# wheatstone_bridge_board.net
KiCad netlist of a schematic drawn in EAGLE
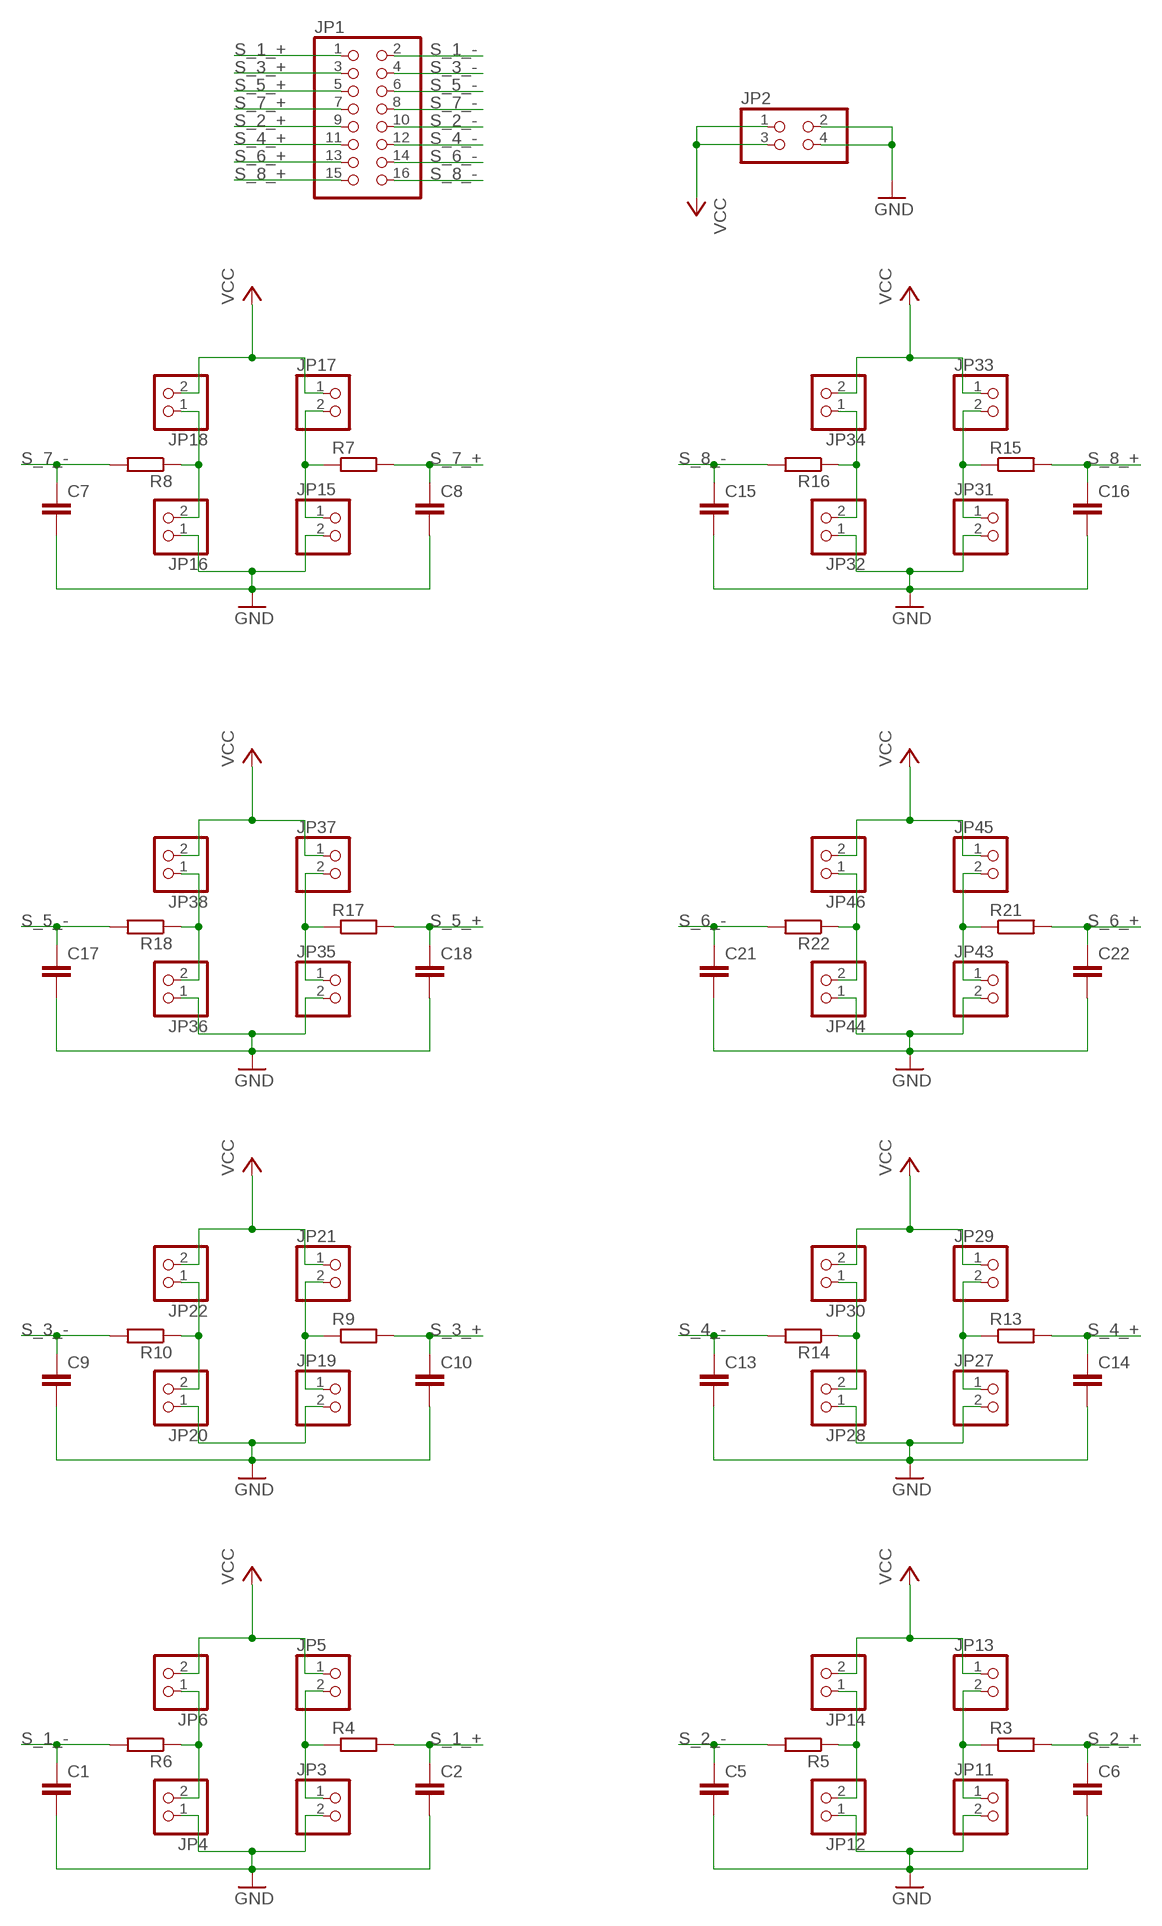
[diagram p0: schematic, sheet 1]

(export (version "E")
  (design (tool "Eeschema 10.0.6"))
  (components
    (comp (ref "C1")
      (value "C-EU025-050X050")
      (footprint "eagle-import:C025-050X050")
      (libsource (lib "eagle-import") (part "C-EU025-050X050"))
    )
    (comp (ref "C2")
      (value "C-EU025-050X050")
      (footprint "eagle-import:C025-050X050")
      (libsource (lib "eagle-import") (part "C-EU025-050X050"))
    )
    (comp (ref "C5")
      (value "C-EU025-050X050")
      (footprint "eagle-import:C025-050X050")
      (libsource (lib "eagle-import") (part "C-EU025-050X050"))
    )
    (comp (ref "C6")
      (value "C-EU025-050X050")
      (footprint "eagle-import:C025-050X050")
      (libsource (lib "eagle-import") (part "C-EU025-050X050"))
    )
    (comp (ref "C7")
      (value "C-EU025-050X050")
      (footprint "eagle-import:C025-050X050")
      (libsource (lib "eagle-import") (part "C-EU025-050X050"))
    )
    (comp (ref "C8")
      (value "C-EU025-050X050")
      (footprint "eagle-import:C025-050X050")
      (libsource (lib "eagle-import") (part "C-EU025-050X050"))
    )
    (comp (ref "C9")
      (value "C-EU025-050X050")
      (footprint "eagle-import:C025-050X050")
      (libsource (lib "eagle-import") (part "C-EU025-050X050"))
    )
    (comp (ref "C10")
      (value "C-EU025-050X050")
      (footprint "eagle-import:C025-050X050")
      (libsource (lib "eagle-import") (part "C-EU025-050X050"))
    )
    (comp (ref "C13")
      (value "C-EU025-050X050")
      (footprint "eagle-import:C025-050X050")
      (libsource (lib "eagle-import") (part "C-EU025-050X050"))
    )
    (comp (ref "C14")
      (value "C-EU025-050X050")
      (footprint "eagle-import:C025-050X050")
      (libsource (lib "eagle-import") (part "C-EU025-050X050"))
    )
    (comp (ref "C15")
      (value "C-EU025-050X050")
      (footprint "eagle-import:C025-050X050")
      (libsource (lib "eagle-import") (part "C-EU025-050X050"))
    )
    (comp (ref "C16")
      (value "C-EU025-050X050")
      (footprint "eagle-import:C025-050X050")
      (libsource (lib "eagle-import") (part "C-EU025-050X050"))
    )
    (comp (ref "C17")
      (value "C-EU025-050X050")
      (footprint "eagle-import:C025-050X050")
      (libsource (lib "eagle-import") (part "C-EU025-050X050"))
    )
    (comp (ref "C18")
      (value "C-EU025-050X050")
      (footprint "eagle-import:C025-050X050")
      (libsource (lib "eagle-import") (part "C-EU025-050X050"))
    )
    (comp (ref "C21")
      (value "C-EU025-050X050")
      (footprint "eagle-import:C025-050X050")
      (libsource (lib "eagle-import") (part "C-EU025-050X050"))
    )
    (comp (ref "C22")
      (value "C-EU025-050X050")
      (footprint "eagle-import:C025-050X050")
      (libsource (lib "eagle-import") (part "C-EU025-050X050"))
    )
    (comp (ref "JP1")
      (value "PINHD-2X8/90")
      (footprint "eagle-import:2X08_90")
      (libsource (lib "eagle-import") (part "PINHD-2X8/90"))
    )
    (comp (ref "JP2")
      (value "PINHD-2X2/90")
      (footprint "eagle-import:2X02_90")
      (libsource (lib "eagle-import") (part "PINHD-2X2/90"))
    )
    (comp (ref "JP3")
      (value "PINHD-1X2")
      (footprint "eagle-import:1X02")
      (libsource (lib "eagle-import") (part "PINHD-1X2"))
    )
    (comp (ref "JP4")
      (value "PINHD-1X2")
      (footprint "eagle-import:1X02")
      (libsource (lib "eagle-import") (part "PINHD-1X2"))
    )
    (comp (ref "JP5")
      (value "PINHD-1X2")
      (footprint "eagle-import:1X02")
      (libsource (lib "eagle-import") (part "PINHD-1X2"))
    )
    (comp (ref "JP6")
      (value "PINHD-1X2")
      (footprint "eagle-import:1X02")
      (libsource (lib "eagle-import") (part "PINHD-1X2"))
    )
    (comp (ref "JP11")
      (value "PINHD-1X2")
      (footprint "eagle-import:1X02")
      (libsource (lib "eagle-import") (part "PINHD-1X2"))
    )
    (comp (ref "JP12")
      (value "PINHD-1X2")
      (footprint "eagle-import:1X02")
      (libsource (lib "eagle-import") (part "PINHD-1X2"))
    )
    (comp (ref "JP13")
      (value "PINHD-1X2")
      (footprint "eagle-import:1X02")
      (libsource (lib "eagle-import") (part "PINHD-1X2"))
    )
    (comp (ref "JP14")
      (value "PINHD-1X2")
      (footprint "eagle-import:1X02")
      (libsource (lib "eagle-import") (part "PINHD-1X2"))
    )
    (comp (ref "JP15")
      (value "PINHD-1X2")
      (footprint "eagle-import:1X02")
      (libsource (lib "eagle-import") (part "PINHD-1X2"))
    )
    (comp (ref "JP16")
      (value "PINHD-1X2")
      (footprint "eagle-import:1X02")
      (libsource (lib "eagle-import") (part "PINHD-1X2"))
    )
    (comp (ref "JP17")
      (value "PINHD-1X2")
      (footprint "eagle-import:1X02")
      (libsource (lib "eagle-import") (part "PINHD-1X2"))
    )
    (comp (ref "JP18")
      (value "PINHD-1X2")
      (footprint "eagle-import:1X02")
      (libsource (lib "eagle-import") (part "PINHD-1X2"))
    )
    (comp (ref "JP19")
      (value "PINHD-1X2")
      (footprint "eagle-import:1X02")
      (libsource (lib "eagle-import") (part "PINHD-1X2"))
    )
    (comp (ref "JP20")
      (value "PINHD-1X2")
      (footprint "eagle-import:1X02")
      (libsource (lib "eagle-import") (part "PINHD-1X2"))
    )
    (comp (ref "JP21")
      (value "PINHD-1X2")
      (footprint "eagle-import:1X02")
      (libsource (lib "eagle-import") (part "PINHD-1X2"))
    )
    (comp (ref "JP22")
      (value "PINHD-1X2")
      (footprint "eagle-import:1X02")
      (libsource (lib "eagle-import") (part "PINHD-1X2"))
    )
    (comp (ref "JP27")
      (value "PINHD-1X2")
      (footprint "eagle-import:1X02")
      (libsource (lib "eagle-import") (part "PINHD-1X2"))
    )
    (comp (ref "JP28")
      (value "PINHD-1X2")
      (footprint "eagle-import:1X02")
      (libsource (lib "eagle-import") (part "PINHD-1X2"))
    )
    (comp (ref "JP29")
      (value "PINHD-1X2")
      (footprint "eagle-import:1X02")
      (libsource (lib "eagle-import") (part "PINHD-1X2"))
    )
    (comp (ref "JP30")
      (value "PINHD-1X2")
      (footprint "eagle-import:1X02")
      (libsource (lib "eagle-import") (part "PINHD-1X2"))
    )
    (comp (ref "JP31")
      (value "PINHD-1X2")
      (footprint "eagle-import:1X02")
      (libsource (lib "eagle-import") (part "PINHD-1X2"))
    )
    (comp (ref "JP32")
      (value "PINHD-1X2")
      (footprint "eagle-import:1X02")
      (libsource (lib "eagle-import") (part "PINHD-1X2"))
    )
    (comp (ref "JP33")
      (value "PINHD-1X2")
      (footprint "eagle-import:1X02")
      (libsource (lib "eagle-import") (part "PINHD-1X2"))
    )
    (comp (ref "JP34")
      (value "PINHD-1X2")
      (footprint "eagle-import:1X02")
      (libsource (lib "eagle-import") (part "PINHD-1X2"))
    )
    (comp (ref "JP35")
      (value "PINHD-1X2")
      (footprint "eagle-import:1X02")
      (libsource (lib "eagle-import") (part "PINHD-1X2"))
    )
    (comp (ref "JP36")
      (value "PINHD-1X2")
      (footprint "eagle-import:1X02")
      (libsource (lib "eagle-import") (part "PINHD-1X2"))
    )
    (comp (ref "JP37")
      (value "PINHD-1X2")
      (footprint "eagle-import:1X02")
      (libsource (lib "eagle-import") (part "PINHD-1X2"))
    )
    (comp (ref "JP38")
      (value "PINHD-1X2")
      (footprint "eagle-import:1X02")
      (libsource (lib "eagle-import") (part "PINHD-1X2"))
    )
    (comp (ref "JP43")
      (value "PINHD-1X2")
      (footprint "eagle-import:1X02")
      (libsource (lib "eagle-import") (part "PINHD-1X2"))
    )
    (comp (ref "JP44")
      (value "PINHD-1X2")
      (footprint "eagle-import:1X02")
      (libsource (lib "eagle-import") (part "PINHD-1X2"))
    )
    (comp (ref "JP45")
      (value "PINHD-1X2")
      (footprint "eagle-import:1X02")
      (libsource (lib "eagle-import") (part "PINHD-1X2"))
    )
    (comp (ref "JP46")
      (value "PINHD-1X2")
      (footprint "eagle-import:1X02")
      (libsource (lib "eagle-import") (part "PINHD-1X2"))
    )
    (comp (ref "R3")
      (value "R-EU_R0603")
      (footprint "eagle-import:R0603")
      (libsource (lib "eagle-import") (part "R-EU_R0603"))
    )
    (comp (ref "R4")
      (value "R-EU_R0603")
      (footprint "eagle-import:R0603")
      (libsource (lib "eagle-import") (part "R-EU_R0603"))
    )
    (comp (ref "R5")
      (value "R-EU_R0603")
      (footprint "eagle-import:R0603")
      (libsource (lib "eagle-import") (part "R-EU_R0603"))
    )
    (comp (ref "R6")
      (value "R-EU_R0603")
      (footprint "eagle-import:R0603")
      (libsource (lib "eagle-import") (part "R-EU_R0603"))
    )
    (comp (ref "R7")
      (value "R-EU_R0603")
      (footprint "eagle-import:R0603")
      (libsource (lib "eagle-import") (part "R-EU_R0603"))
    )
    (comp (ref "R8")
      (value "R-EU_R0603")
      (footprint "eagle-import:R0603")
      (libsource (lib "eagle-import") (part "R-EU_R0603"))
    )
    (comp (ref "R9")
      (value "R-EU_R0603")
      (footprint "eagle-import:R0603")
      (libsource (lib "eagle-import") (part "R-EU_R0603"))
    )
    (comp (ref "R10")
      (value "R-EU_R0603")
      (footprint "eagle-import:R0603")
      (libsource (lib "eagle-import") (part "R-EU_R0603"))
    )
    (comp (ref "R13")
      (value "R-EU_R0603")
      (footprint "eagle-import:R0603")
      (libsource (lib "eagle-import") (part "R-EU_R0603"))
    )
    (comp (ref "R14")
      (value "R-EU_R0603")
      (footprint "eagle-import:R0603")
      (libsource (lib "eagle-import") (part "R-EU_R0603"))
    )
    (comp (ref "R15")
      (value "R-EU_R0603")
      (footprint "eagle-import:R0603")
      (libsource (lib "eagle-import") (part "R-EU_R0603"))
    )
    (comp (ref "R16")
      (value "R-EU_R0603")
      (footprint "eagle-import:R0603")
      (libsource (lib "eagle-import") (part "R-EU_R0603"))
    )
    (comp (ref "R17")
      (value "R-EU_R0603")
      (footprint "eagle-import:R0603")
      (libsource (lib "eagle-import") (part "R-EU_R0603"))
    )
    (comp (ref "R18")
      (value "R-EU_R0603")
      (footprint "eagle-import:R0603")
      (libsource (lib "eagle-import") (part "R-EU_R0603"))
    )
    (comp (ref "R21")
      (value "R-EU_R0603")
      (footprint "eagle-import:R0603")
      (libsource (lib "eagle-import") (part "R-EU_R0603"))
    )
    (comp (ref "R22")
      (value "R-EU_R0603")
      (footprint "eagle-import:R0603")
      (libsource (lib "eagle-import") (part "R-EU_R0603"))
    )
  )
  (nets
    (net (code "1") (name "/S_1_+") (class "Default")
      (node (ref "C2") (pin "1") (pinfunction "1_1") (pintype "passive"))
      (node (ref "JP1") (pin "1") (pinfunction "1_1") (pintype "passive"))
      (node (ref "R4") (pin "2") (pinfunction "2_2") (pintype "passive"))
    )
    (net (code "2") (name "/S_1_-") (class "Default")
      (node (ref "C1") (pin "1") (pinfunction "1_1") (pintype "passive"))
      (node (ref "JP1") (pin "2") (pinfunction "2_2") (pintype "passive"))
      (node (ref "R6") (pin "2") (pinfunction "2_2") (pintype "passive"))
    )
    (net (code "3") (name "/S_2_+") (class "Default")
      (node (ref "C6") (pin "1") (pinfunction "1_1") (pintype "passive"))
      (node (ref "JP1") (pin "9") (pinfunction "9_9") (pintype "passive"))
      (node (ref "R3") (pin "2") (pinfunction "2_2") (pintype "passive"))
    )
    (net (code "4") (name "/S_2_-") (class "Default")
      (node (ref "C5") (pin "1") (pinfunction "1_1") (pintype "passive"))
      (node (ref "JP1") (pin "10") (pinfunction "10_10") (pintype "passive"))
      (node (ref "R5") (pin "2") (pinfunction "2_2") (pintype "passive"))
    )
    (net (code "5") (name "/S_3_+") (class "Default")
      (node (ref "C10") (pin "1") (pinfunction "1_1") (pintype "passive"))
      (node (ref "JP1") (pin "3") (pinfunction "3_3") (pintype "passive"))
      (node (ref "R9") (pin "2") (pinfunction "2_2") (pintype "passive"))
    )
    (net (code "6") (name "/S_3_-") (class "Default")
      (node (ref "C9") (pin "1") (pinfunction "1_1") (pintype "passive"))
      (node (ref "JP1") (pin "4") (pinfunction "4_4") (pintype "passive"))
      (node (ref "R10") (pin "2") (pinfunction "2_2") (pintype "passive"))
    )
    (net (code "7") (name "/S_4_+") (class "Default")
      (node (ref "C14") (pin "1") (pinfunction "1_1") (pintype "passive"))
      (node (ref "JP1") (pin "11") (pinfunction "11_11") (pintype "passive"))
      (node (ref "R13") (pin "2") (pinfunction "2_2") (pintype "passive"))
    )
    (net (code "8") (name "/S_4_-") (class "Default")
      (node (ref "C13") (pin "1") (pinfunction "1_1") (pintype "passive"))
      (node (ref "JP1") (pin "12") (pinfunction "12_12") (pintype "passive"))
      (node (ref "R14") (pin "2") (pinfunction "2_2") (pintype "passive"))
    )
    (net (code "9") (name "/S_5_+") (class "Default")
      (node (ref "C18") (pin "1") (pinfunction "1_1") (pintype "passive"))
      (node (ref "JP1") (pin "5") (pinfunction "5_5") (pintype "passive"))
      (node (ref "R17") (pin "2") (pinfunction "2_2") (pintype "passive"))
    )
    (net (code "10") (name "/S_5_-") (class "Default")
      (node (ref "C17") (pin "1") (pinfunction "1_1") (pintype "passive"))
      (node (ref "JP1") (pin "6") (pinfunction "6_6") (pintype "passive"))
      (node (ref "R18") (pin "2") (pinfunction "2_2") (pintype "passive"))
    )
    (net (code "11") (name "/S_6_+") (class "Default")
      (node (ref "C22") (pin "1") (pinfunction "1_1") (pintype "passive"))
      (node (ref "JP1") (pin "13") (pinfunction "13_13") (pintype "passive"))
      (node (ref "R21") (pin "2") (pinfunction "2_2") (pintype "passive"))
    )
    (net (code "12") (name "/S_6_-") (class "Default")
      (node (ref "C21") (pin "1") (pinfunction "1_1") (pintype "passive"))
      (node (ref "JP1") (pin "14") (pinfunction "14_14") (pintype "passive"))
      (node (ref "R22") (pin "2") (pinfunction "2_2") (pintype "passive"))
    )
    (net (code "13") (name "/S_7_+") (class "Default")
      (node (ref "C8") (pin "1") (pinfunction "1_1") (pintype "passive"))
      (node (ref "JP1") (pin "7") (pinfunction "7_7") (pintype "passive"))
      (node (ref "R7") (pin "2") (pinfunction "2_2") (pintype "passive"))
    )
    (net (code "14") (name "/S_7_-") (class "Default")
      (node (ref "C7") (pin "1") (pinfunction "1_1") (pintype "passive"))
      (node (ref "JP1") (pin "8") (pinfunction "8_8") (pintype "passive"))
      (node (ref "R8") (pin "2") (pinfunction "2_2") (pintype "passive"))
    )
    (net (code "15") (name "/S_8_+") (class "Default")
      (node (ref "C16") (pin "1") (pinfunction "1_1") (pintype "passive"))
      (node (ref "JP1") (pin "15") (pinfunction "15_15") (pintype "passive"))
      (node (ref "R15") (pin "2") (pinfunction "2_2") (pintype "passive"))
    )
    (net (code "16") (name "/S_8_-") (class "Default")
      (node (ref "C15") (pin "1") (pinfunction "1_1") (pintype "passive"))
      (node (ref "JP1") (pin "16") (pinfunction "16_16") (pintype "passive"))
      (node (ref "R16") (pin "2") (pinfunction "2_2") (pintype "passive"))
    )
    (net (code "17") (name "GND") (class "Default")
      (node (ref "C1") (pin "2") (pinfunction "2_2") (pintype "passive"))
      (node (ref "C10") (pin "2") (pinfunction "2_2") (pintype "passive"))
      (node (ref "C13") (pin "2") (pinfunction "2_2") (pintype "passive"))
      (node (ref "C14") (pin "2") (pinfunction "2_2") (pintype "passive"))
      (node (ref "C15") (pin "2") (pinfunction "2_2") (pintype "passive"))
      (node (ref "C16") (pin "2") (pinfunction "2_2") (pintype "passive"))
      (node (ref "C17") (pin "2") (pinfunction "2_2") (pintype "passive"))
      (node (ref "C18") (pin "2") (pinfunction "2_2") (pintype "passive"))
      (node (ref "C2") (pin "2") (pinfunction "2_2") (pintype "passive"))
      (node (ref "C21") (pin "2") (pinfunction "2_2") (pintype "passive"))
      (node (ref "C22") (pin "2") (pinfunction "2_2") (pintype "passive"))
      (node (ref "C5") (pin "2") (pinfunction "2_2") (pintype "passive"))
      (node (ref "C6") (pin "2") (pinfunction "2_2") (pintype "passive"))
      (node (ref "C7") (pin "2") (pinfunction "2_2") (pintype "passive"))
      (node (ref "C8") (pin "2") (pinfunction "2_2") (pintype "passive"))
      (node (ref "C9") (pin "2") (pinfunction "2_2") (pintype "passive"))
      (node (ref "JP11") (pin "2") (pinfunction "2_2") (pintype "passive"))
      (node (ref "JP12") (pin "1") (pinfunction "1_1") (pintype "passive"))
      (node (ref "JP15") (pin "2") (pinfunction "2_2") (pintype "passive"))
      (node (ref "JP16") (pin "1") (pinfunction "1_1") (pintype "passive"))
      (node (ref "JP19") (pin "2") (pinfunction "2_2") (pintype "passive"))
      (node (ref "JP2") (pin "2") (pinfunction "2_2") (pintype "passive"))
      (node (ref "JP2") (pin "4") (pinfunction "4_4") (pintype "passive"))
      (node (ref "JP20") (pin "1") (pinfunction "1_1") (pintype "passive"))
      (node (ref "JP27") (pin "2") (pinfunction "2_2") (pintype "passive"))
      (node (ref "JP28") (pin "1") (pinfunction "1_1") (pintype "passive"))
      (node (ref "JP3") (pin "2") (pinfunction "2_2") (pintype "passive"))
      (node (ref "JP31") (pin "2") (pinfunction "2_2") (pintype "passive"))
      (node (ref "JP32") (pin "1") (pinfunction "1_1") (pintype "passive"))
      (node (ref "JP35") (pin "2") (pinfunction "2_2") (pintype "passive"))
      (node (ref "JP36") (pin "1") (pinfunction "1_1") (pintype "passive"))
      (node (ref "JP4") (pin "1") (pinfunction "1_1") (pintype "passive"))
      (node (ref "JP43") (pin "2") (pinfunction "2_2") (pintype "passive"))
      (node (ref "JP44") (pin "1") (pinfunction "1_1") (pintype "passive"))
    )
    (net (code "18") (name "Net-(JP3-Pad1)") (class "Default")
      (node (ref "JP3") (pin "1") (pinfunction "1_1") (pintype "passive"))
      (node (ref "JP5") (pin "2") (pinfunction "2_2") (pintype "passive"))
      (node (ref "R4") (pin "1") (pinfunction "1_1") (pintype "passive"))
    )
    (net (code "19") (name "Net-(JP4-Pad2)") (class "Default")
      (node (ref "JP4") (pin "2") (pinfunction "2_2") (pintype "passive"))
      (node (ref "JP6") (pin "1") (pinfunction "1_1") (pintype "passive"))
      (node (ref "R6") (pin "1") (pinfunction "1_1") (pintype "passive"))
    )
    (net (code "20") (name "Net-(JP11-Pad1)") (class "Default")
      (node (ref "JP11") (pin "1") (pinfunction "1_1") (pintype "passive"))
      (node (ref "JP13") (pin "2") (pinfunction "2_2") (pintype "passive"))
      (node (ref "R3") (pin "1") (pinfunction "1_1") (pintype "passive"))
    )
    (net (code "21") (name "Net-(JP12-Pad2)") (class "Default")
      (node (ref "JP12") (pin "2") (pinfunction "2_2") (pintype "passive"))
      (node (ref "JP14") (pin "1") (pinfunction "1_1") (pintype "passive"))
      (node (ref "R5") (pin "1") (pinfunction "1_1") (pintype "passive"))
    )
    (net (code "22") (name "Net-(JP15-Pad1)") (class "Default")
      (node (ref "JP15") (pin "1") (pinfunction "1_1") (pintype "passive"))
      (node (ref "JP17") (pin "2") (pinfunction "2_2") (pintype "passive"))
      (node (ref "R7") (pin "1") (pinfunction "1_1") (pintype "passive"))
    )
    (net (code "23") (name "Net-(JP16-Pad2)") (class "Default")
      (node (ref "JP16") (pin "2") (pinfunction "2_2") (pintype "passive"))
      (node (ref "JP18") (pin "1") (pinfunction "1_1") (pintype "passive"))
      (node (ref "R8") (pin "1") (pinfunction "1_1") (pintype "passive"))
    )
    (net (code "24") (name "Net-(JP19-Pad1)") (class "Default")
      (node (ref "JP19") (pin "1") (pinfunction "1_1") (pintype "passive"))
      (node (ref "JP21") (pin "2") (pinfunction "2_2") (pintype "passive"))
      (node (ref "R9") (pin "1") (pinfunction "1_1") (pintype "passive"))
    )
    (net (code "25") (name "Net-(JP20-Pad2)") (class "Default")
      (node (ref "JP20") (pin "2") (pinfunction "2_2") (pintype "passive"))
      (node (ref "JP22") (pin "1") (pinfunction "1_1") (pintype "passive"))
      (node (ref "R10") (pin "1") (pinfunction "1_1") (pintype "passive"))
    )
    (net (code "26") (name "Net-(JP27-Pad1)") (class "Default")
      (node (ref "JP27") (pin "1") (pinfunction "1_1") (pintype "passive"))
      (node (ref "JP29") (pin "2") (pinfunction "2_2") (pintype "passive"))
      (node (ref "R13") (pin "1") (pinfunction "1_1") (pintype "passive"))
    )
    (net (code "27") (name "Net-(JP28-Pad2)") (class "Default")
      (node (ref "JP28") (pin "2") (pinfunction "2_2") (pintype "passive"))
      (node (ref "JP30") (pin "1") (pinfunction "1_1") (pintype "passive"))
      (node (ref "R14") (pin "1") (pinfunction "1_1") (pintype "passive"))
    )
    (net (code "28") (name "Net-(JP31-Pad1)") (class "Default")
      (node (ref "JP31") (pin "1") (pinfunction "1_1") (pintype "passive"))
      (node (ref "JP33") (pin "2") (pinfunction "2_2") (pintype "passive"))
      (node (ref "R15") (pin "1") (pinfunction "1_1") (pintype "passive"))
    )
    (net (code "29") (name "Net-(JP32-Pad2)") (class "Default")
      (node (ref "JP32") (pin "2") (pinfunction "2_2") (pintype "passive"))
      (node (ref "JP34") (pin "1") (pinfunction "1_1") (pintype "passive"))
      (node (ref "R16") (pin "1") (pinfunction "1_1") (pintype "passive"))
    )
    (net (code "30") (name "Net-(JP35-Pad1)") (class "Default")
      (node (ref "JP35") (pin "1") (pinfunction "1_1") (pintype "passive"))
      (node (ref "JP37") (pin "2") (pinfunction "2_2") (pintype "passive"))
      (node (ref "R17") (pin "1") (pinfunction "1_1") (pintype "passive"))
    )
    (net (code "31") (name "Net-(JP36-Pad2)") (class "Default")
      (node (ref "JP36") (pin "2") (pinfunction "2_2") (pintype "passive"))
      (node (ref "JP38") (pin "1") (pinfunction "1_1") (pintype "passive"))
      (node (ref "R18") (pin "1") (pinfunction "1_1") (pintype "passive"))
    )
    (net (code "32") (name "Net-(JP43-Pad1)") (class "Default")
      (node (ref "JP43") (pin "1") (pinfunction "1_1") (pintype "passive"))
      (node (ref "JP45") (pin "2") (pinfunction "2_2") (pintype "passive"))
      (node (ref "R21") (pin "1") (pinfunction "1_1") (pintype "passive"))
    )
    (net (code "33") (name "Net-(JP44-Pad2)") (class "Default")
      (node (ref "JP44") (pin "2") (pinfunction "2_2") (pintype "passive"))
      (node (ref "JP46") (pin "1") (pinfunction "1_1") (pintype "passive"))
      (node (ref "R22") (pin "1") (pinfunction "1_1") (pintype "passive"))
    )
    (net (code "34") (name "VCC") (class "Default")
      (node (ref "JP13") (pin "1") (pinfunction "1_1") (pintype "passive"))
      (node (ref "JP14") (pin "2") (pinfunction "2_2") (pintype "passive"))
      (node (ref "JP17") (pin "1") (pinfunction "1_1") (pintype "passive"))
      (node (ref "JP18") (pin "2") (pinfunction "2_2") (pintype "passive"))
      (node (ref "JP2") (pin "1") (pinfunction "1_1") (pintype "passive"))
      (node (ref "JP2") (pin "3") (pinfunction "3_3") (pintype "passive"))
      (node (ref "JP21") (pin "1") (pinfunction "1_1") (pintype "passive"))
      (node (ref "JP22") (pin "2") (pinfunction "2_2") (pintype "passive"))
      (node (ref "JP29") (pin "1") (pinfunction "1_1") (pintype "passive"))
      (node (ref "JP30") (pin "2") (pinfunction "2_2") (pintype "passive"))
      (node (ref "JP33") (pin "1") (pinfunction "1_1") (pintype "passive"))
      (node (ref "JP34") (pin "2") (pinfunction "2_2") (pintype "passive"))
      (node (ref "JP37") (pin "1") (pinfunction "1_1") (pintype "passive"))
      (node (ref "JP38") (pin "2") (pinfunction "2_2") (pintype "passive"))
      (node (ref "JP45") (pin "1") (pinfunction "1_1") (pintype "passive"))
      (node (ref "JP46") (pin "2") (pinfunction "2_2") (pintype "passive"))
      (node (ref "JP5") (pin "1") (pinfunction "1_1") (pintype "passive"))
      (node (ref "JP6") (pin "2") (pinfunction "2_2") (pintype "passive"))
    )
  )
)
